# gyro_volt-divide.net
KiCad netlist of a schematic drawn in EAGLE
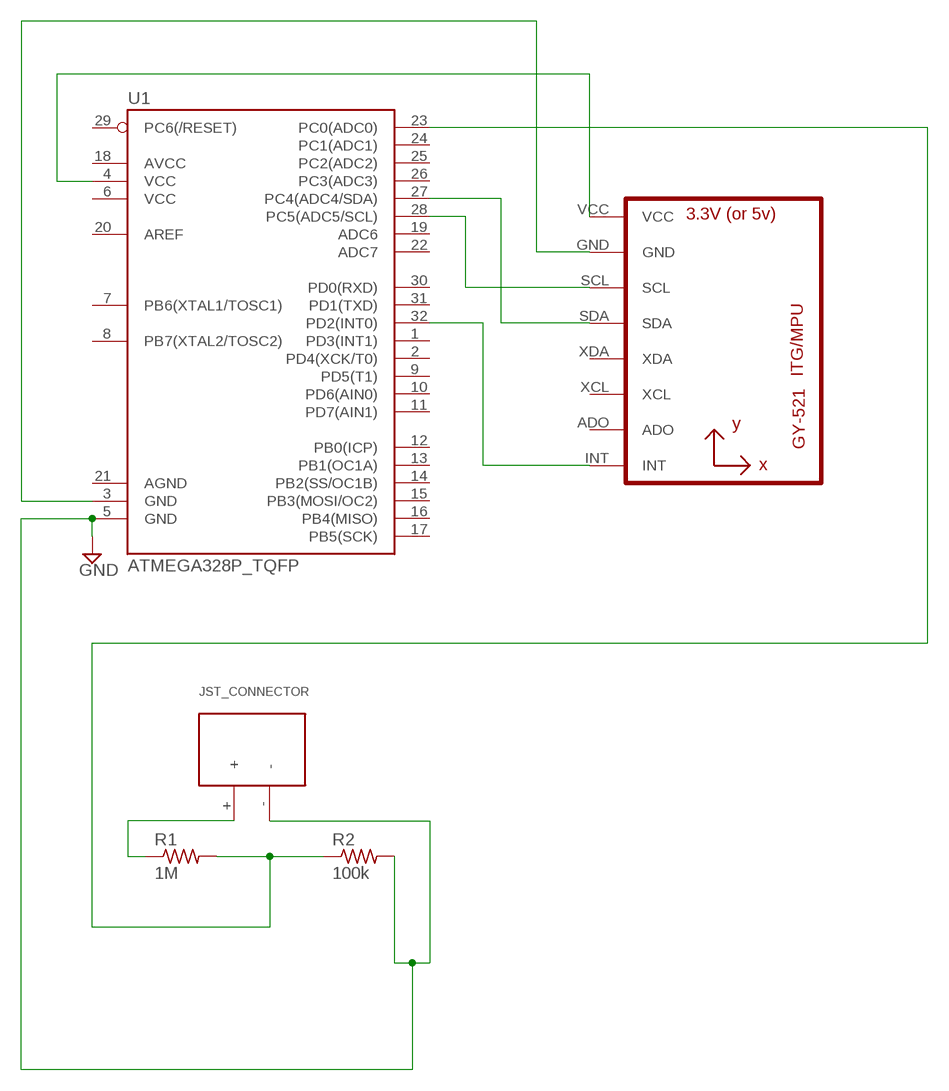
[diagram p0: schematic, sheet 1]

(export (version "E")
  (design (tool "Eeschema 10.0.6"))
  (components
    (comp (ref "R1")
      (value "1M")
      (footprint "eagle-import:R0603")
      (libsource (lib "eagle-import") (part "R-US_R0603"))
    )
    (comp (ref "R2")
      (value "100k")
      (footprint "eagle-import:R0603")
      (libsource (lib "eagle-import") (part "R-US_R0603"))
    )
    (comp (ref "U$1")
      (value "JST_CONNECTOR_FEMALE")
      (footprint "eagle-import:JST_CONNECTOR_FEMALE")
      (libsource (lib "eagle-import") (part "JST_CONNECTOR_FEMALE"))
    )
    (comp (ref "U1")
      (value "ATMEGA328P_TQFP")
      (footprint "eagle-import:TQFP32-08")
      (libsource (lib "eagle-import") (part "ATMEGA328P_TQFP"))
    )
    (comp (ref "U2")
      (value "GY-521MPU6050")
      (footprint "eagle-import:GY-521")
      (libsource (lib "eagle-import") (part "GY-521MPU6050"))
    )
  )
  (nets
    (net (code "1") (name "GND") (class "Default")
      (node (ref "R2") (pin "2") (pinfunction "2_2") (pintype "passive"))
      (node (ref "U$1") (pin "-") (pinfunction "-_-") (pintype "bidirectional"))
      (node (ref "U1") (pin "5") (pinfunction "GND_5") (pintype "bidirectional"))
    )
    (net (code "2") (name "Net-(R1-Pad1)") (class "Default")
      (node (ref "R1") (pin "1") (pinfunction "1_1") (pintype "passive"))
      (node (ref "U$1") (pin "+") (pinfunction "+_+") (pintype "bidirectional"))
    )
    (net (code "3") (name "Net-(U1-GND-Pad3)") (class "Default")
      (node (ref "U1") (pin "3") (pinfunction "GND_3") (pintype "bidirectional"))
      (node (ref "U2") (pin "GND") (pinfunction "GND_GND") (pintype "bidirectional"))
    )
    (net (code "4") (name "Net-(U1-PC0(ADC0))") (class "Default")
      (node (ref "R1") (pin "2") (pinfunction "2_2") (pintype "passive"))
      (node (ref "R2") (pin "1") (pinfunction "1_1") (pintype "passive"))
      (node (ref "U1") (pin "23") (pinfunction "PC0(ADC0)_23") (pintype "bidirectional"))
    )
    (net (code "5") (name "Net-(U1-PC4(ADC4{slash}SDA))") (class "Default")
      (node (ref "U1") (pin "27") (pinfunction "PC4(ADC4/SDA)_27") (pintype "bidirectional"))
      (node (ref "U2") (pin "SDA") (pinfunction "SDA_SDA") (pintype "bidirectional"))
    )
    (net (code "6") (name "Net-(U1-PC5(ADC5{slash}SCL))") (class "Default")
      (node (ref "U1") (pin "28") (pinfunction "PC5(ADC5/SCL)_28") (pintype "bidirectional"))
      (node (ref "U2") (pin "SCL") (pinfunction "SCL_SCL") (pintype "bidirectional"))
    )
    (net (code "7") (name "Net-(U1-PD2(INT0))") (class "Default")
      (node (ref "U1") (pin "32") (pinfunction "PD2(INT0)_32") (pintype "bidirectional"))
      (node (ref "U2") (pin "INT") (pinfunction "INT_INT") (pintype "bidirectional"))
    )
    (net (code "8") (name "Net-(U1-VCC-Pad4)") (class "Default")
      (node (ref "U1") (pin "4") (pinfunction "VCC_4") (pintype "bidirectional"))
      (node (ref "U2") (pin "VCC") (pinfunction "VCC_VCC") (pintype "bidirectional"))
    )
    (net (code "9") (name "unconnected-(U1-ADC6-Pad19)") (class "Default")
      (node (ref "U1") (pin "19") (pinfunction "ADC6_19") (pintype "bidirectional"))
    )
    (net (code "10") (name "unconnected-(U1-ADC7-Pad22)") (class "Default")
      (node (ref "U1") (pin "22") (pinfunction "ADC7_22") (pintype "bidirectional"))
    )
    (net (code "11") (name "unconnected-(U1-AGND-Pad21)") (class "Default")
      (node (ref "U1") (pin "21") (pinfunction "AGND_21") (pintype "bidirectional"))
    )
    (net (code "12") (name "unconnected-(U1-AREF-Pad20)") (class "Default")
      (node (ref "U1") (pin "20") (pinfunction "AREF_20") (pintype "bidirectional"))
    )
    (net (code "13") (name "unconnected-(U1-AVCC-Pad18)") (class "Default")
      (node (ref "U1") (pin "18") (pinfunction "AVCC_18") (pintype "bidirectional"))
    )
    (net (code "14") (name "unconnected-(U1-PB0(ICP)-Pad12)") (class "Default")
      (node (ref "U1") (pin "12") (pinfunction "PB0(ICP)_12") (pintype "bidirectional"))
    )
    (net (code "15") (name "unconnected-(U1-PB1(OC1A)-Pad13)") (class "Default")
      (node (ref "U1") (pin "13") (pinfunction "PB1(OC1A)_13") (pintype "bidirectional"))
    )
    (net (code "16") (name "unconnected-(U1-PB2(SS{slash}OC1B)-Pad14)") (class "Default")
      (node (ref "U1") (pin "14") (pinfunction "PB2(SS/OC1B)_14") (pintype "bidirectional"))
    )
    (net (code "17") (name "unconnected-(U1-PB3(MOSI{slash}OC2)-Pad15)") (class "Default")
      (node (ref "U1") (pin "15") (pinfunction "PB3(MOSI/OC2)_15") (pintype "bidirectional"))
    )
    (net (code "18") (name "unconnected-(U1-PB4(MISO)-Pad16)") (class "Default")
      (node (ref "U1") (pin "16") (pinfunction "PB4(MISO)_16") (pintype "bidirectional"))
    )
    (net (code "19") (name "unconnected-(U1-PB5(SCK)-Pad17)") (class "Default")
      (node (ref "U1") (pin "17") (pinfunction "PB5(SCK)_17") (pintype "bidirectional"))
    )
    (net (code "20") (name "unconnected-(U1-PB6(XTAL1{slash}TOSC1)-Pad7)") (class "Default")
      (node (ref "U1") (pin "7") (pinfunction "PB6(XTAL1/TOSC1)_7") (pintype "bidirectional"))
    )
    (net (code "21") (name "unconnected-(U1-PB7(XTAL2{slash}TOSC2)-Pad8)") (class "Default")
      (node (ref "U1") (pin "8") (pinfunction "PB7(XTAL2/TOSC2)_8") (pintype "bidirectional"))
    )
    (net (code "22") (name "unconnected-(U1-PC1(ADC1)-Pad24)") (class "Default")
      (node (ref "U1") (pin "24") (pinfunction "PC1(ADC1)_24") (pintype "bidirectional"))
    )
    (net (code "23") (name "unconnected-(U1-PC2(ADC2)-Pad25)") (class "Default")
      (node (ref "U1") (pin "25") (pinfunction "PC2(ADC2)_25") (pintype "bidirectional"))
    )
    (net (code "24") (name "unconnected-(U1-PC3(ADC3)-Pad26)") (class "Default")
      (node (ref "U1") (pin "26") (pinfunction "PC3(ADC3)_26") (pintype "bidirectional"))
    )
    (net (code "25") (name "unconnected-(U1-PC6({slash}RESET)-Pad29)") (class "Default")
      (node (ref "U1") (pin "29") (pinfunction "PC6(/RESET)_29") (pintype "bidirectional"))
    )
    (net (code "26") (name "unconnected-(U1-PD0(RXD)-Pad30)") (class "Default")
      (node (ref "U1") (pin "30") (pinfunction "PD0(RXD)_30") (pintype "bidirectional"))
    )
    (net (code "27") (name "unconnected-(U1-PD1(TXD)-Pad31)") (class "Default")
      (node (ref "U1") (pin "31") (pinfunction "PD1(TXD)_31") (pintype "bidirectional"))
    )
    (net (code "28") (name "unconnected-(U1-PD3(INT1)-Pad1)") (class "Default")
      (node (ref "U1") (pin "1") (pinfunction "PD3(INT1)_1") (pintype "bidirectional"))
    )
    (net (code "29") (name "unconnected-(U1-PD4(XCK{slash}T0)-Pad2)") (class "Default")
      (node (ref "U1") (pin "2") (pinfunction "PD4(XCK/T0)_2") (pintype "bidirectional"))
    )
    (net (code "30") (name "unconnected-(U1-PD5(T1)-Pad9)") (class "Default")
      (node (ref "U1") (pin "9") (pinfunction "PD5(T1)_9") (pintype "bidirectional"))
    )
    (net (code "31") (name "unconnected-(U1-PD6(AIN0)-Pad10)") (class "Default")
      (node (ref "U1") (pin "10") (pinfunction "PD6(AIN0)_10") (pintype "bidirectional"))
    )
    (net (code "32") (name "unconnected-(U1-PD7(AIN1)-Pad11)") (class "Default")
      (node (ref "U1") (pin "11") (pinfunction "PD7(AIN1)_11") (pintype "bidirectional"))
    )
    (net (code "33") (name "unconnected-(U1-VCC-Pad6)") (class "Default")
      (node (ref "U1") (pin "6") (pinfunction "VCC_6") (pintype "bidirectional"))
    )
    (net (code "34") (name "unconnected-(U2-PadADO)") (class "Default")
      (node (ref "U2") (pin "ADO") (pinfunction "ADO_ADO") (pintype "bidirectional"))
    )
    (net (code "35") (name "unconnected-(U2-PadXCL)") (class "Default")
      (node (ref "U2") (pin "XCL") (pinfunction "XCL_XCL") (pintype "bidirectional"))
    )
    (net (code "36") (name "unconnected-(U2-PadXDA)") (class "Default")
      (node (ref "U2") (pin "XDA") (pinfunction "XDA_XDA") (pintype "bidirectional"))
    )
  )
)
